# Powerboard_Rev2_Sheet.net
KiCad netlist of a schematic drawn in Altium Designer
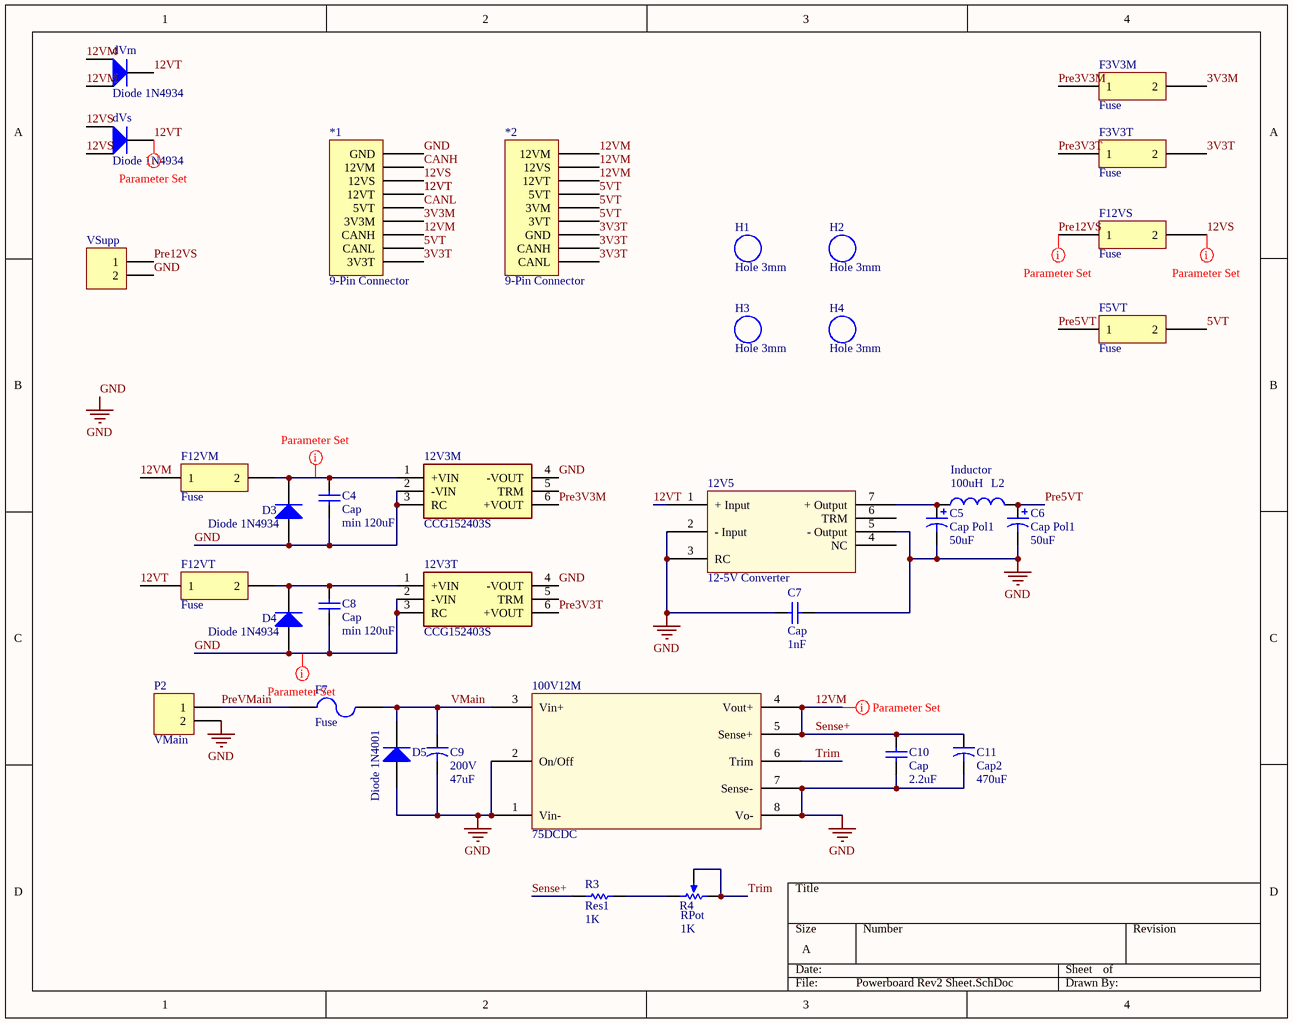
[diagram p0: Powerboard Rev2 Sheet.SchDoc]

(export (version "E")
  (design (tool "Eeschema 10.0.6"))
  (components
    (comp (ref "*1")
      (value "9-Pin Connector")
      (footprint "9-Pin")
      (libsource (lib "SolarGators") (part "9-Pin Connector"))
    )
    (comp (ref "*2")
      (value "9-Pin Connector")
      (footprint "9-Pin")
      (libsource (lib "SolarGators") (part "9-Pin Connector"))
    )
    (comp (ref "12V3M")
      (value "CCG152403S")
      (footprint "SamacSys:CCG152403S")
      (description "Power Supply")
      (libsource (lib "*") (part "CCG152403S"))
    )
    (comp (ref "12V3T")
      (value "CCG152403S")
      (footprint "SamacSys:CCG152403S")
      (description "Power Supply")
      (libsource (lib "*") (part "CCG152403S"))
    )
    (comp (ref "12V5")
      (value "12-5V Converter")
      (footprint "CC6-1205SF-E")
      (libsource (lib "SolarGators") (part "12-5V Converter"))
    )
    (comp (ref "100V12M")
      (value "75DCDC")
      (footprint "100DC12")
      (libsource (lib "SolarGators") (part "75DCDC"))
    )
    (comp (ref "C4")
      (value "Cap")
      (footprint "200mm Cap")
      (description "Capacitor")
      (fields (field (name "ALTIUM_VALUE") "min 120uF") (field (name "PUBLISHER") "Altium Limited"))
      (libsource (lib "Miscellaneous Devices") (part "Cap"))
    )
    (comp (ref "C5")
      (value "Cap Pol1")
      (footprint "200milCap")
      (description "Polarized Capacitor (Radial)")
      (fields (field (name "ALTIUM_VALUE") "50uF") (field (name "PUBLISHER") "Altium Limited"))
      (libsource (lib "Miscellaneous Devices") (part "Cap Pol1"))
    )
    (comp (ref "C6")
      (value "Cap Pol1")
      (footprint "200milCap")
      (description "Polarized Capacitor (Radial)")
      (fields (field (name "ALTIUM_VALUE") "50uF") (field (name "PUBLISHER") "Altium Limited"))
      (libsource (lib "Miscellaneous Devices") (part "Cap Pol1"))
    )
    (comp (ref "C7")
      (value "Cap")
      (footprint "100milCap")
      (description "Capacitor")
      (fields (field (name "ALTIUM_VALUE") "1nF") (field (name "PUBLISHER") "Altium Limited"))
      (libsource (lib "Miscellaneous Devices") (part "Cap"))
    )
    (comp (ref "C8")
      (value "Cap")
      (footprint "200mm Cap")
      (description "Capacitor")
      (fields (field (name "ALTIUM_VALUE") "min 120uF") (field (name "PUBLISHER") "Altium Limited"))
      (libsource (lib "Miscellaneous Devices") (part "Cap"))
    )
    (comp (ref "C9")
      (value "200V")
      (footprint "200milCap")
      (description "Capacitor")
      (fields (field (name "ALTIUM_VALUE") "47uF") (field (name "PUBLISHER") "Altium Limited"))
      (libsource (lib "Miscellaneous Devices") (part "Cap2"))
    )
    (comp (ref "C10")
      (value "Cap")
      (footprint "100milCap")
      (description "Capacitor")
      (fields (field (name "ALTIUM_VALUE") "2.2uF") (field (name "PUBLISHER") "Altium Limited"))
      (libsource (lib "Miscellaneous Devices") (part "Cap"))
    )
    (comp (ref "C11")
      (value "Cap2")
      (footprint "200milCap")
      (description "Capacitor")
      (fields (field (name "ALTIUM_VALUE") "470uF") (field (name "PUBLISHER") "Altium Limited"))
      (libsource (lib "Miscellaneous Devices") (part "Cap2"))
    )
    (comp (ref "D3")
      (value "Diode 1N4934")
      (footprint "2pinDiode")
      (description "1 Amp Fast Recovery Rectifier")
      (fields (field (name "PUBLISHER") "Altium Limited"))
      (libsource (lib "Miscellaneous Devices") (part "Diode 1N4934"))
    )
    (comp (ref "D4")
      (value "Diode 1N4934")
      (footprint "2pinDiode")
      (description "1 Amp Fast Recovery Rectifier")
      (fields (field (name "PUBLISHER") "Altium Limited"))
      (libsource (lib "Miscellaneous Devices") (part "Diode 1N4934"))
    )
    (comp (ref "D5")
      (value "Diode 1N4001")
      (footprint "2pinDiode")
      (description "1 Amp General Purpose Rectifier")
      (fields (field (name "PUBLISHER") "Altium Limited"))
      (libsource (lib "Miscellaneous Devices") (part "Diode 1N4001"))
    )
    (comp (ref "dVm")
      (value "Diode 1N4934")
      (footprint "3pindiode")
      (description "1 Amp Fast Recovery Rectifier")
      (fields (field (name "PUBLISHER") "Altium Limited"))
      (libsource (lib "") (part "Diode 1N4934_1"))
    )
    (comp (ref "dVs")
      (value "Diode 1N4934")
      (footprint "3pindiode")
      (description "1 Amp Fast Recovery Rectifier")
      (fields (field (name "PUBLISHER") "Altium Limited"))
      (libsource (lib "") (part "Diode 1N4934_1"))
    )
    (comp (ref "F3V3M")
      (value "Fuse")
      (footprint "Fuse Hilder")
      (libsource (lib "SolarGators") (part "Fuse"))
    )
    (comp (ref "F3V3T")
      (value "Fuse")
      (footprint "Fuse Hilder")
      (libsource (lib "SolarGators") (part "Fuse"))
    )
    (comp (ref "F5VT") (value "Fuse") (footprint "Fuse Hilder") (libsource (lib "SolarGators") (part "Fuse")))
    (comp (ref "F7")
      (value "Fuse")
      (footprint "Fuse Hilder")
      (fields (field (name "PUBLISHER") "Altium Limited"))
      (libsource (lib "Miscellaneous Devices") (part "Fuse 2"))
    )
    (comp (ref "F12VM")
      (value "Fuse")
      (footprint "Fuse Hilder")
      (libsource (lib "SolarGators") (part "Fuse"))
    )
    (comp (ref "F12VS")
      (value "Fuse")
      (footprint "Fuse Hilder")
      (libsource (lib "SolarGators") (part "Fuse"))
    )
    (comp (ref "F12VT")
      (value "Fuse")
      (footprint "Fuse Hilder")
      (libsource (lib "SolarGators") (part "Fuse"))
    )
    (comp (ref "H1")
      (value "Hole 3mm")
      (footprint "Hole 3mm")
      (libsource (lib "ECE LIB new") (part "Hole 3mm"))
    )
    (comp (ref "H2")
      (value "Hole 3mm")
      (footprint "Hole 3mm")
      (libsource (lib "ECE LIB new") (part "Hole 3mm"))
    )
    (comp (ref "H3")
      (value "Hole 3mm")
      (footprint "Hole 3mm")
      (libsource (lib "ECE LIB new") (part "Hole 3mm"))
    )
    (comp (ref "H4")
      (value "Hole 3mm")
      (footprint "Hole 3mm")
      (libsource (lib "ECE LIB new") (part "Hole 3mm"))
    )
    (comp (ref "L2")
      (value "Inductor")
      (footprint "Inductor")
      (fields (field (name "ALTIUM_VALUE") "100uH") (field (name "PUBLISHER") "Altium Limited"))
      (libsource (lib "ECE LIB new") (part "Inductor"))
    )
    (comp (ref "P2")
      (value "VMain")
      (footprint "HDR1X2")
      (description "Header, 2-Pin")
      (fields (field (name "PUBLISHER") "Altium Limited"))
      (libsource (lib "Miscellaneous Connectors") (part "Header 2"))
    )
    (comp (ref "R3")
      (value "Res1")
      (footprint "AXIAL-0.3")
      (description "Resistor")
      (fields (field (name "ALTIUM_VALUE") "1K") (field (name "PUBLISHER") "Altium Limited"))
      (libsource (lib "Miscellaneous Devices") (part "Res1"))
    )
    (comp (ref "R4")
      (value "RPot")
      (footprint "POT inline wide")
      (description "Potentiometer")
      (fields (field (name "ALTIUM_VALUE") "1K") (field (name "PUBLISHER") "Altium Limited"))
      (libsource (lib "ECE LIB new") (part "RPot_3"))
    )
    (comp (ref "VSupp")
      (value "~")
      (footprint "HDR1X2")
      (description "Header, 2-Pin")
      (fields (field (name "PUBLISHER") "Altium Limited"))
      (libsource (lib "Miscellaneous Connectors") (part "Header 2"))
    )
  )
  (nets
    (net (code "1") (name "/3V3M") (class "Default")
      (node (ref "*1") (pin "6") (pinfunction "3VT_6") (pintype "passive"))
      (node (ref "F3V3M") (pin "2") (pinfunction "2_2") (pintype "passive"))
    )
    (net (code "2") (name "/3V3T") (class "Default")
      (node (ref "*1") (pin "9") (pinfunction "CANL_9") (pintype "passive"))
      (node (ref "*2") (pin "7") (pinfunction "GND_7") (pintype "passive"))
      (node (ref "*2") (pin "8") (pinfunction "CANH_8") (pintype "passive"))
      (node (ref "*2") (pin "9") (pinfunction "CANL_9") (pintype "passive"))
      (node (ref "F3V3T") (pin "2") (pinfunction "2_2") (pintype "passive"))
    )
    (net (code "3") (name "/5VT") (class "Default")
      (node (ref "*1") (pin "8") (pinfunction "CANH_8") (pintype "passive"))
      (node (ref "*2") (pin "4") (pinfunction "5VT_4") (pintype "passive"))
      (node (ref "*2") (pin "5") (pinfunction "3VM_5") (pintype "passive"))
      (node (ref "*2") (pin "6") (pinfunction "3VT_6") (pintype "passive"))
      (node (ref "F5VT") (pin "2") (pinfunction "2_2") (pintype "passive"))
    )
    (net (code "4") (name "/12VM") (class "Default")
      (node (ref "*1") (pin "7") (pinfunction "GND_7") (pintype "passive"))
      (node (ref "*2") (pin "1") (pinfunction "12VM_1") (pintype "passive"))
      (node (ref "*2") (pin "2") (pinfunction "12VS_2") (pintype "passive"))
      (node (ref "*2") (pin "3") (pinfunction "12VT_3") (pintype "passive"))
      (node (ref "100V12M") (pin "4") (pinfunction "Vout+_4") (pintype "passive"))
      (node (ref "100V12M") (pin "5") (pinfunction "Sense+_5") (pintype "passive"))
      (node (ref "C10") (pin "2") (pinfunction "2_2") (pintype "passive"))
      (node (ref "C11") (pin "1") (pinfunction "1_1") (pintype "passive"))
      (node (ref "F12VM") (pin "1") (pinfunction "1_1") (pintype "passive"))
      (node (ref "R3") (pin "1") (pinfunction "1_1") (pintype "passive"))
      (node (ref "dVm") (pin "1") (pinfunction "A_1") (pintype "passive"))
      (node (ref "dVm") (pin "3") (pinfunction "A_3") (pintype "passive"))
    )
    (net (code "5") (name "/12VS") (class "Default")
      (node (ref "*1") (pin "3") (pinfunction "12VT_3") (pintype "passive"))
      (node (ref "F12VS") (pin "2") (pinfunction "2_2") (pintype "passive"))
      (node (ref "dVs") (pin "1") (pinfunction "A_1") (pintype "passive"))
      (node (ref "dVs") (pin "3") (pinfunction "A_3") (pintype "passive"))
    )
    (net (code "6") (name "/12VT") (class "Default")
      (node (ref "*1") (pin "4") (pinfunction "5VT_4") (pintype "passive"))
      (node (ref "12V5") (pin "1") (pinfunction "+_Input_1") (pintype "passive"))
      (node (ref "F12VT") (pin "1") (pinfunction "1_1") (pintype "passive"))
      (node (ref "dVm") (pin "2") (pinfunction "K_2") (pintype "passive"))
      (node (ref "dVs") (pin "2") (pinfunction "K_2") (pintype "passive"))
    )
    (net (code "7") (name "/CANH") (class "Default")
      (node (ref "*1") (pin "2") (pinfunction "12VS_2") (pintype "passive"))
    )
    (net (code "8") (name "/CANL") (class "Default")
      (node (ref "*1") (pin "5") (pinfunction "3VM_5") (pintype "passive"))
    )
    (net (code "9") (name "/Pre3V3M") (class "Default")
      (node (ref "12V3M") (pin "6") (pinfunction "+VOUT_6") (pintype "passive"))
      (node (ref "F3V3M") (pin "1") (pinfunction "1_1") (pintype "passive"))
    )
    (net (code "10") (name "/Pre3V3T") (class "Default")
      (node (ref "12V3T") (pin "6") (pinfunction "+VOUT_6") (pintype "passive"))
      (node (ref "F3V3T") (pin "1") (pinfunction "1_1") (pintype "passive"))
    )
    (net (code "11") (name "/Pre5VT") (class "Default")
      (node (ref "C6") (pin "1") (pinfunction "1_1") (pintype "passive"))
      (node (ref "F5VT") (pin "1") (pinfunction "1_1") (pintype "passive"))
      (node (ref "L2") (pin "2") (pinfunction "2_2") (pintype "passive"))
    )
    (net (code "12") (name "/Pre12VS") (class "Default")
      (node (ref "F12VS") (pin "1") (pinfunction "1_1") (pintype "passive"))
      (node (ref "VSupp") (pin "1") (pinfunction "1_1") (pintype "passive"))
    )
    (net (code "13") (name "/PreVMain") (class "Default")
      (node (ref "F7") (pin "1") (pinfunction "1_1") (pintype "passive"))
      (node (ref "P2") (pin "1") (pinfunction "1_1") (pintype "passive"))
    )
    (net (code "14") (name "/Trim") (class "Default")
      (node (ref "100V12M") (pin "6") (pinfunction "Trim_6") (pintype "passive"))
      (node (ref "R4") (pin "1") (pinfunction "TOP_1") (pintype "passive"))
      (node (ref "R4") (pin "2") (pinfunction "TAP_2") (pintype "passive"))
    )
    (net (code "15") (name "/VMain") (class "Default")
      (node (ref "100V12M") (pin "3") (pinfunction "Vin+_3") (pintype "passive"))
      (node (ref "C9") (pin "1") (pinfunction "1_1") (pintype "passive"))
      (node (ref "D5") (pin "2") (pinfunction "K_2") (pintype "passive"))
      (node (ref "F7") (pin "2") (pinfunction "2_2") (pintype "passive"))
    )
    (net (code "16") (name "GND") (class "Default")
      (node (ref "*1") (pin "1") (pinfunction "12VM_1") (pintype "passive"))
      (node (ref "100V12M") (pin "1") (pinfunction "Vin-_1") (pintype "passive"))
      (node (ref "100V12M") (pin "2") (pinfunction "On/Off_2") (pintype "passive"))
      (node (ref "100V12M") (pin "7") (pinfunction "Sense-_7") (pintype "passive"))
      (node (ref "100V12M") (pin "8") (pinfunction "Vo-_8") (pintype "passive"))
      (node (ref "12V3M") (pin "2") (pinfunction "-VIN_2") (pintype "passive"))
      (node (ref "12V3M") (pin "3") (pinfunction "RC_3") (pintype "passive"))
      (node (ref "12V3M") (pin "4") (pinfunction "-VOUT_4") (pintype "passive"))
      (node (ref "12V3T") (pin "2") (pinfunction "-VIN_2") (pintype "passive"))
      (node (ref "12V3T") (pin "3") (pinfunction "RC_3") (pintype "passive"))
      (node (ref "12V3T") (pin "4") (pinfunction "-VOUT_4") (pintype "passive"))
      (node (ref "12V5") (pin "2") (pinfunction "-_Input_2") (pintype "passive"))
      (node (ref "12V5") (pin "3") (pinfunction "RC_3") (pintype "passive"))
      (node (ref "12V5") (pin "5") (pinfunction "-_Output_5") (pintype "passive"))
      (node (ref "C10") (pin "1") (pinfunction "1_1") (pintype "passive"))
      (node (ref "C11") (pin "2") (pinfunction "2_2") (pintype "passive"))
      (node (ref "C4") (pin "1") (pinfunction "1_1") (pintype "passive"))
      (node (ref "C5") (pin "2") (pinfunction "2_2") (pintype "passive"))
      (node (ref "C6") (pin "2") (pinfunction "2_2") (pintype "passive"))
      (node (ref "C7") (pin "1") (pinfunction "1_1") (pintype "passive"))
      (node (ref "C7") (pin "2") (pinfunction "2_2") (pintype "passive"))
      (node (ref "C8") (pin "1") (pinfunction "1_1") (pintype "passive"))
      (node (ref "C9") (pin "2") (pinfunction "2_2") (pintype "passive"))
      (node (ref "D3") (pin "1") (pinfunction "A_1") (pintype "passive"))
      (node (ref "D4") (pin "1") (pinfunction "A_1") (pintype "passive"))
      (node (ref "D5") (pin "1") (pinfunction "A_1") (pintype "passive"))
      (node (ref "P2") (pin "2") (pinfunction "2_2") (pintype "passive"))
      (node (ref "VSupp") (pin "2") (pinfunction "2_2") (pintype "passive"))
    )
    (net (code "17") (name "Net-(12V3M-+VIN)") (class "Default")
      (node (ref "12V3M") (pin "1") (pinfunction "+VIN_1") (pintype "passive"))
      (node (ref "C4") (pin "2") (pinfunction "2_2") (pintype "passive"))
      (node (ref "D3") (pin "2") (pinfunction "K_2") (pintype "passive"))
      (node (ref "F12VM") (pin "2") (pinfunction "2_2") (pintype "passive"))
    )
    (net (code "18") (name "Net-(12V3T-+VIN)") (class "Default")
      (node (ref "12V3T") (pin "1") (pinfunction "+VIN_1") (pintype "passive"))
      (node (ref "C8") (pin "2") (pinfunction "2_2") (pintype "passive"))
      (node (ref "D4") (pin "2") (pinfunction "K_2") (pintype "passive"))
      (node (ref "F12VT") (pin "2") (pinfunction "2_2") (pintype "passive"))
    )
    (net (code "19") (name "Net-(12V5-+_Output)") (class "Default")
      (node (ref "12V5") (pin "7") (pinfunction "+_Output_7") (pintype "passive"))
      (node (ref "C5") (pin "1") (pinfunction "1_1") (pintype "passive"))
      (node (ref "L2") (pin "1") (pinfunction "1_1") (pintype "passive"))
    )
    (net (code "20") (name "Net-(R4-BOT)") (class "Default")
      (node (ref "R3") (pin "2") (pinfunction "2_2") (pintype "passive"))
      (node (ref "R4") (pin "3") (pinfunction "BOT_3") (pintype "passive"))
    )
    (net (code "21") (name "unconnected-(12V3M-TRM-Pad5)") (class "Default")
      (node (ref "12V3M") (pin "5") (pinfunction "TRM_5") (pintype "passive"))
    )
    (net (code "22") (name "unconnected-(12V3T-TRM-Pad5)") (class "Default")
      (node (ref "12V3T") (pin "5") (pinfunction "TRM_5") (pintype "passive"))
    )
    (net (code "23") (name "unconnected-(12V5-NC-Pad4)") (class "Default")
      (node (ref "12V5") (pin "4") (pinfunction "NC_4") (pintype "passive"))
    )
    (net (code "24") (name "unconnected-(12V5-TRM-Pad6)") (class "Default")
      (node (ref "12V5") (pin "6") (pinfunction "TRM_6") (pintype "passive"))
    )
  )
)
